# PHY6222_32_0_4__V1_7.net
KiCad netlist of a schematic drawn in Altium Designer
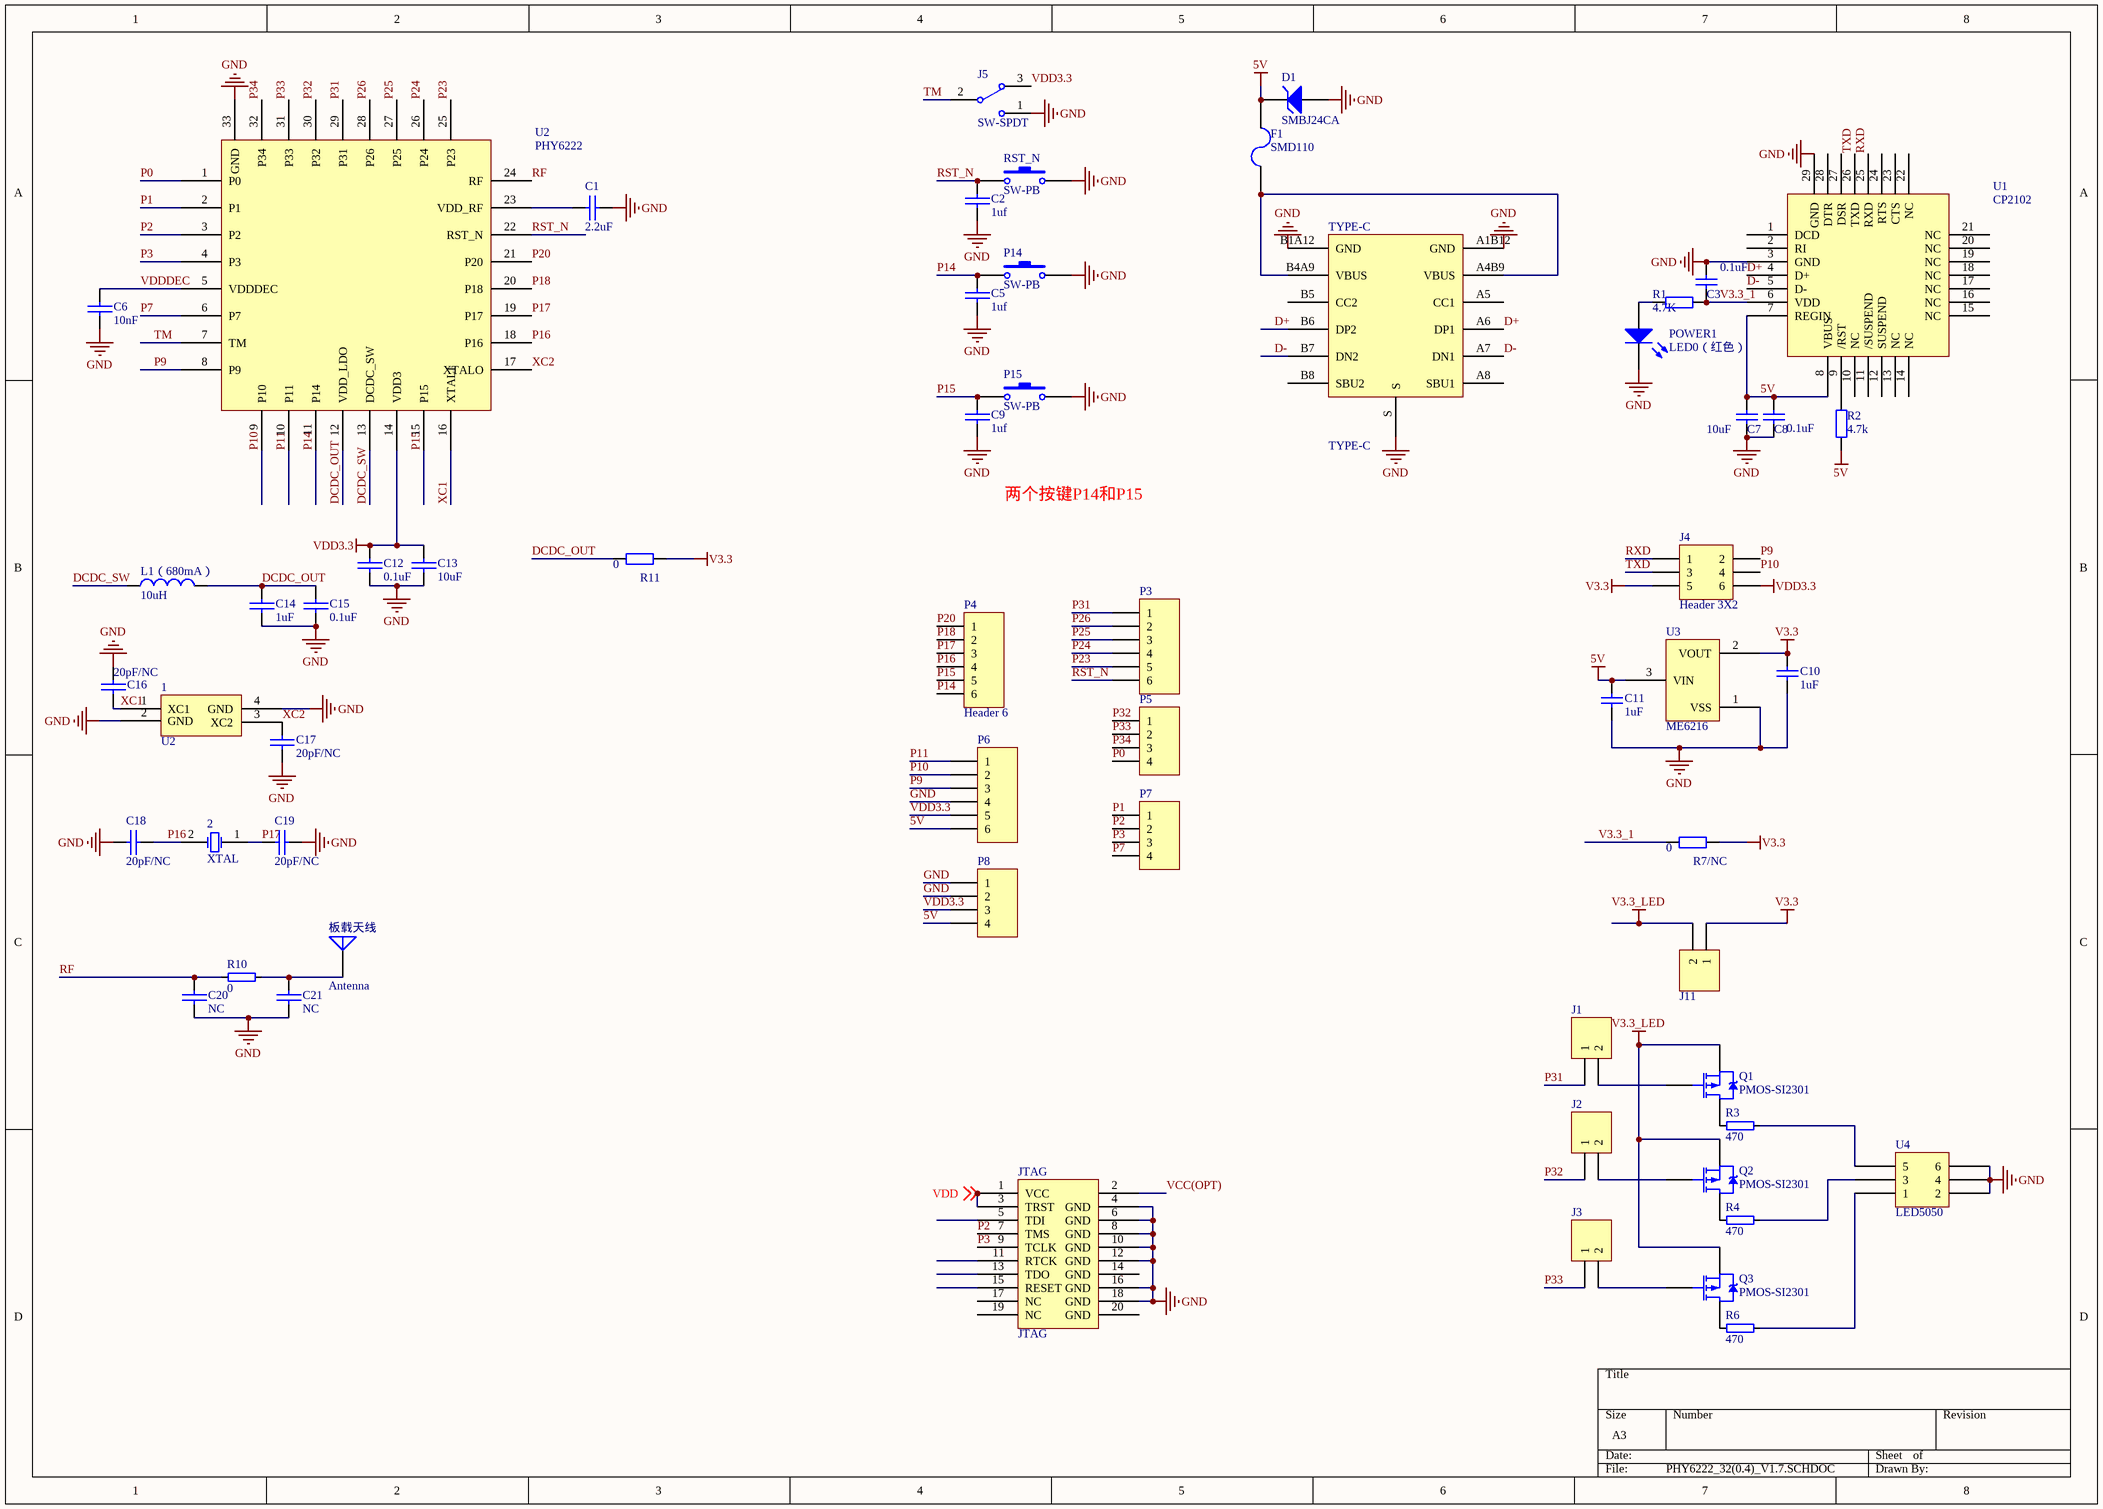
[diagram p0: PHY6222_32(0.4)_V1.7.SCHDOC]

(export (version "E")
  (design (tool "Eeschema 10.0.6"))
  (components
    (comp (ref "1") (value "U2") (footprint "3225") (libsource (lib "RF_APP") (part "3225")))
    (comp (ref "2")
      (value "XTAL")
      (footprint "3215   32.768k")
      (description "Crystal Oscillator")
      (fields (field (name "PUBLISHER") "Altium Limited"))
      (libsource (lib "Miscellaneous Devices") (part "XTAL"))
    )
    (comp (ref "C1") (value "2.2uF") (footprint "C0402") (libsource (lib "RF_0603") (part "电容瓷片")))
    (comp (ref "C2") (value "1uf") (footprint "C0402") (libsource (lib "PCB_Project") (part "电容瓷片")))
    (comp (ref "C3")
      (value "0.1uF")
      (footprint "C0402")
      (description "Capacitor")
      (fields (field (name "PUBLISHER") "Altium Limited"))
      (libsource (lib "Miscellaneous Devices") (part "Cap"))
    )
    (comp (ref "C5") (value "1uf") (footprint "C0402") (libsource (lib "PCB_Project") (part "电容瓷片")))
    (comp (ref "C6") (value "10nF") (footprint "C0402") (libsource (lib "RF_0603") (part "电容瓷片")))
    (comp (ref "C7")
      (value "10uF")
      (footprint "0603R")
      (description "Capacitor")
      (fields (field (name "PUBLISHER") "Altium Limited"))
      (libsource (lib "Miscellaneous Devices") (part "Cap"))
    )
    (comp (ref "C8")
      (value "0.1uF")
      (footprint "C0402")
      (description "Capacitor")
      (fields (field (name "PUBLISHER") "Altium Limited"))
      (libsource (lib "Miscellaneous Devices") (part "Cap"))
    )
    (comp (ref "C9") (value "1uf") (footprint "C0402") (libsource (lib "PCB_Project") (part "电容瓷片")))
    (comp (ref "C10")
      (value "1uF")
      (footprint "C0402")
      (description "Capacitor")
      (fields (field (name "PUBLISHER") "Altium Limited"))
      (libsource (lib "Miscellaneous Devices") (part "Cap"))
    )
    (comp (ref "C11")
      (value "1uF")
      (footprint "C0402")
      (description "Capacitor")
      (fields (field (name "PUBLISHER") "Altium Limited"))
      (libsource (lib "Miscellaneous Devices") (part "Cap"))
    )
    (comp (ref "C12") (value "0.1uF") (footprint "C0402") (libsource (lib "PCB_Project") (part "电容瓷片")))
    (comp (ref "C13") (value "10uF") (footprint "C0603") (libsource (lib "PCB_Project") (part "电容瓷片")))
    (comp (ref "C14") (value "1uF") (footprint "C0402") (libsource (lib "RF_0603") (part "电容瓷片")))
    (comp (ref "C15") (value "0.1uF") (footprint "C0402") (libsource (lib "RF_0603") (part "电容瓷片")))
    (comp (ref "C16") (value "20pF/NC") (footprint "C0402") (libsource (lib "PCB_Project") (part "电容瓷片")))
    (comp (ref "C17") (value "20pF/NC") (footprint "C0402") (libsource (lib "PCB_Project") (part "电容瓷片")))
    (comp (ref "C18") (value "20pF/NC") (footprint "C0402") (libsource (lib "PCB_Project") (part "电容瓷片")))
    (comp (ref "C19") (value "20pF/NC") (footprint "C0402") (libsource (lib "PCB_Project") (part "电容瓷片")))
    (comp (ref "C20") (value "NC") (footprint "C0402") (libsource (lib "RF_0603") (part "电容瓷片")))
    (comp (ref "C21") (value "NC") (footprint "C0402") (libsource (lib "RF_0603") (part "电容瓷片")))
    (comp (ref "D1")
      (value "SMBJ24CA")
      (footprint "1N5819S")
      (description "Zener Diode")
      (fields (field (name "PUBLISHER") "*"))
      (libsource (lib "*") (part "D Zener"))
    )
    (comp (ref "F1")
      (value "SMD110")
      (footprint "1812")
      (description "Fuse")
      (libsource (lib "RC-sheet") (part "FUSE2"))
    )
    (comp (ref "J1")
      (value "Header 2")
      (footprint "HDR1X2")
      (description "Header, 2-Pin")
      (fields (field (name "PUBLISHER") "Altium Limited"))
      (libsource (lib "Miscellaneous Connectors") (part "Header 2"))
    )
    (comp (ref "J2")
      (value "Header 2")
      (footprint "HDR1X2")
      (description "Header, 2-Pin")
      (fields (field (name "PUBLISHER") "Altium Limited"))
      (libsource (lib "Miscellaneous Connectors") (part "Header 2"))
    )
    (comp (ref "J3")
      (value "Header 2")
      (footprint "HDR1X2")
      (description "Header, 2-Pin")
      (fields (field (name "PUBLISHER") "Altium Limited"))
      (libsource (lib "Miscellaneous Connectors") (part "Header 2"))
    )
    (comp (ref "J4")
      (value "Header 3X2")
      (footprint "HDR2X3")
      (description "Header, 3-Pin, Dual row")
      (fields (field (name "PUBLISHER") "Altium Limited"))
      (libsource (lib "Miscellaneous Connectors") (part "Header 3X2"))
    )
    (comp (ref "J5")
      (value "SW-SPDT")
      (footprint "HDR1X3")
      (description "SPDT Subminiature Toggle Switch, Right Angle Mounting, Vertical Actuation")
      (fields (field (name "PUBLISHER") "Altium Limited"))
      (libsource (lib "Miscellaneous Devices") (part "SW-SPDT"))
    )
    (comp (ref "J11")
      (value "Header 2")
      (footprint "HDR1X2")
      (description "Header, 2-Pin")
      (fields (field (name "PUBLISHER") "Altium Limited"))
      (libsource (lib "") (part "Header 2_1"))
    )
    (comp (ref "JTAG") (value "JTAG") (footprint "JTAG1") (libsource (lib "PCB_Project") (part "JTAG")))
    (comp (ref "L1（680mA）")
      (value "10uH")
      (footprint "SMD2520")
      (description "电感")
      (fields (field (name "PUBLISHER") "Altium Limited"))
      (libsource (lib "RF_0603") (part "电感"))
    )
    (comp (ref "P3")
      (value "MHDR1X6")
      (footprint "HDR1X6")
      (description "Header, 6-Pin")
      (fields (field (name "PUBLISHER") "Altium Limited"))
      (libsource (lib "Miscellaneous Connectors") (part "MHDR1X6"))
    )
    (comp (ref "P4")
      (value "Header 6")
      (footprint "HDR1X6")
      (description "Header, 6-Pin")
      (fields (field (name "PUBLISHER") "Altium Limited"))
      (libsource (lib "Phyplus") (part "Header 6"))
    )
    (comp (ref "P5")
      (value "MHDR1X4")
      (footprint "HDR1X4")
      (description "Header, 4-Pin")
      (fields (field (name "PUBLISHER") "Altium Limited"))
      (libsource (lib "Miscellaneous Connectors") (part "MHDR1X4"))
    )
    (comp (ref "P6")
      (value "MHDR1X6")
      (footprint "HDR1X6")
      (description "Header, 6-Pin")
      (fields (field (name "PUBLISHER") "Altium Limited"))
      (libsource (lib "Miscellaneous Connectors") (part "MHDR1X6"))
    )
    (comp (ref "P7")
      (value "MHDR1X4")
      (footprint "HDR1X4")
      (description "Header, 4-Pin")
      (fields (field (name "PUBLISHER") "Altium Limited"))
      (libsource (lib "Miscellaneous Connectors") (part "MHDR1X4"))
    )
    (comp (ref "P8")
      (value "MHDR1X4")
      (footprint "HDR1X4")
      (description "Header, 4-Pin")
      (fields (field (name "PUBLISHER") "Altium Limited"))
      (libsource (lib "Miscellaneous Connectors") (part "MHDR1X4"))
    )
    (comp (ref "P14")
      (value "SW-PB")
      (footprint "SW  3*4*2")
      (description "Switch")
      (fields (field (name "PUBLISHER") "Altium Limited"))
      (libsource (lib "Miscellaneous Devices") (part "SW-PB"))
    )
    (comp (ref "P15")
      (value "SW-PB")
      (footprint "SW  3*4*2")
      (description "Switch")
      (fields (field (name "PUBLISHER") "Altium Limited"))
      (libsource (lib "Miscellaneous Devices") (part "SW-PB"))
    )
    (comp (ref "POWER1")
      (value "LED0（红色）")
      (footprint "LED0603")
      (description "Typical INFRARED GaAs LED")
      (fields (field (name "PUBLISHER") "Altium Limited"))
      (libsource (lib "Miscellaneous Devices") (part "LED0"))
    )
    (comp (ref "Q1")
      (value "PMOS-SI2301")
      (footprint "SOT-23")
      (description "P-Channel Power MOSFET")
      (fields (field (name "PUBLISHER") "Altium Limited"))
      (libsource (lib "Miscellaneous Devices") (part "PMOS-2"))
    )
    (comp (ref "Q2")
      (value "PMOS-SI2301")
      (footprint "SOT-23")
      (description "P-Channel Power MOSFET")
      (fields (field (name "PUBLISHER") "Altium Limited"))
      (libsource (lib "Miscellaneous Devices") (part "PMOS-2"))
    )
    (comp (ref "Q3")
      (value "PMOS-SI2301")
      (footprint "SOT-23")
      (description "P-Channel Power MOSFET")
      (fields (field (name "PUBLISHER") "Altium Limited"))
      (libsource (lib "Miscellaneous Devices") (part "PMOS-2"))
    )
    (comp (ref "R1")
      (value "4.7K")
      (footprint "R0402")
      (description "Resistor")
      (fields (field (name "PUBLISHER") "Altium Limited"))
      (libsource (lib "") (part "Res2_1"))
    )
    (comp (ref "R2")
      (value "4.7k")
      (footprint "R0402")
      (description "Resistor")
      (fields (field (name "PUBLISHER") "Altium Limited"))
      (libsource (lib "Miscellaneous Devices") (part "Res2"))
    )
    (comp (ref "R3") (value "470") (footprint "R0402") (libsource (lib "RF_0603") (part "电阻贴片")))
    (comp (ref "R4") (value "470") (footprint "R0402") (libsource (lib "RF_0603") (part "电阻贴片")))
    (comp (ref "R6") (value "470") (footprint "R0402") (libsource (lib "RF_0603") (part "电阻贴片")))
    (comp (ref "R7/NC")
      (value "0")
      (footprint "R0603")
      (description "Resistor")
      (fields (field (name "Comment") "4.7K") (field (name "PUBLISHER") "Altium Limited"))
      (libsource (lib "") (part "Res2_1"))
    )
    (comp (ref "R10") (value "0") (footprint "R0402") (libsource (lib "RF_0603") (part "电阻贴片")))
    (comp (ref "R11")
      (value "0")
      (footprint "R0603")
      (description "Resistor")
      (fields (field (name "Comment") "4.7K") (field (name "PUBLISHER") "Altium Limited"))
      (libsource (lib "") (part "Res2_1"))
    )
    (comp (ref "RST_N")
      (value "SW-PB")
      (footprint "SW  3*4*2")
      (description "Switch")
      (fields (field (name "PUBLISHER") "Altium Limited"))
      (libsource (lib "Miscellaneous Devices") (part "SW-PB"))
    )
    (comp (ref "TYPE-C") (value "TYPE-C") (footprint "TYPE-C") (libsource (lib "Phyplus") (part "TYPE-C")))
    (comp (ref "U1") (value "CP2102") (footprint "CP2102") (libsource (lib "Phyplus") (part "cp2102")))
    (comp (ref "U2")
      (value "PHY6222")
      (footprint "QFN32_0.4")
      (libsource (lib "Phyplus") (part "QFN32-1202"))
    )
    (comp (ref "U3") (value "ME6216") (footprint "SOT-23") (libsource (lib "Phyplus") (part "ME6216")))
    (comp (ref "U4") (value "LED5050") (footprint "LED5050") (libsource (lib "PCB_Project") (part "LED5050")))
    (comp (ref "板载天线")
      (value "Antenna")
      (footprint "PIN1")
      (description "Generic Antenna")
      (fields (field (name "PUBLISHER") "Altium Limited"))
      (libsource (lib "Miscellaneous Devices") (part "Antenna"))
    )
  )
  (nets
    (net (code "1") (name "/D+") (class "Default")
      (node (ref "TYPE-C") (pin "A6") (pinfunction "DP1_A6") (pintype "passive"))
      (node (ref "TYPE-C") (pin "B6") (pinfunction "DP2_B6") (pintype "passive"))
      (node (ref "U1") (pin "4") (pinfunction "D+_4") (pintype "passive"))
    )
    (net (code "2") (name "/D-") (class "Default")
      (node (ref "TYPE-C") (pin "A7") (pinfunction "DN1_A7") (pintype "passive"))
      (node (ref "TYPE-C") (pin "B7") (pinfunction "DN2_B7") (pintype "passive"))
      (node (ref "U1") (pin "5") (pinfunction "D-_5") (pintype "passive"))
    )
    (net (code "3") (name "/DCDC_OUT") (class "Default")
      (node (ref "C14") (pin "1") (pinfunction "1_1") (pintype "passive"))
      (node (ref "C15") (pin "1") (pinfunction "1_1") (pintype "passive"))
      (node (ref "L1（680mA）") (pin "2") (pinfunction "2_2") (pintype "passive"))
      (node (ref "R11") (pin "1") (pinfunction "1_1") (pintype "passive"))
      (node (ref "U2") (pin "12") (pinfunction "VDD_LDO_12") (pintype "passive"))
    )
    (net (code "4") (name "/DCDC_SW") (class "Default")
      (node (ref "L1（680mA）") (pin "1") (pinfunction "1_1") (pintype "passive"))
      (node (ref "U2") (pin "13") (pinfunction "DCDC_SW_13") (pintype "passive"))
    )
    (net (code "5") (name "/P0") (class "Default")
      (node (ref "P5") (pin "4") (pinfunction "4_4") (pintype "passive"))
      (node (ref "U2") (pin "1") (pinfunction "P0_1") (pintype "passive"))
    )
    (net (code "6") (name "/P1") (class "Default")
      (node (ref "P7") (pin "1") (pinfunction "1_1") (pintype "passive"))
      (node (ref "U2") (pin "2") (pinfunction "P1_2") (pintype "passive"))
    )
    (net (code "7") (name "/P2") (class "Default")
      (node (ref "JTAG") (pin "7") (pinfunction "TMS_7") (pintype "passive"))
      (node (ref "P7") (pin "2") (pinfunction "2_2") (pintype "passive"))
      (node (ref "U2") (pin "3") (pinfunction "P2_3") (pintype "passive"))
    )
    (net (code "8") (name "/P3") (class "Default")
      (node (ref "JTAG") (pin "9") (pinfunction "TCLK_9") (pintype "passive"))
      (node (ref "P7") (pin "3") (pinfunction "3_3") (pintype "passive"))
      (node (ref "U2") (pin "4") (pinfunction "P3_4") (pintype "passive"))
    )
    (net (code "9") (name "/P7") (class "Default")
      (node (ref "P7") (pin "4") (pinfunction "4_4") (pintype "passive"))
      (node (ref "U2") (pin "6") (pinfunction "P7_6") (pintype "passive"))
    )
    (net (code "10") (name "/P9") (class "Default")
      (node (ref "J4") (pin "2") (pinfunction "2_2") (pintype "passive"))
      (node (ref "P6") (pin "3") (pinfunction "3_3") (pintype "passive"))
      (node (ref "U2") (pin "8") (pinfunction "P9_8") (pintype "passive"))
    )
    (net (code "11") (name "/P10") (class "Default")
      (node (ref "J4") (pin "4") (pinfunction "4_4") (pintype "passive"))
      (node (ref "P6") (pin "2") (pinfunction "2_2") (pintype "passive"))
      (node (ref "U2") (pin "9") (pinfunction "P10_9") (pintype "passive"))
    )
    (net (code "12") (name "/P11") (class "Default")
      (node (ref "P6") (pin "1") (pinfunction "1_1") (pintype "passive"))
      (node (ref "U2") (pin "10") (pinfunction "P11_10") (pintype "passive"))
    )
    (net (code "13") (name "/P14") (class "Default")
      (node (ref "C5") (pin "1") (pinfunction "1_1") (pintype "passive"))
      (node (ref "P14") (pin "1") (pinfunction "1_1") (pintype "passive"))
      (node (ref "P4") (pin "6") (pinfunction "6_6") (pintype "passive"))
      (node (ref "U2") (pin "11") (pinfunction "P14_11") (pintype "passive"))
    )
    (net (code "14") (name "/P15") (class "Default")
      (node (ref "C9") (pin "1") (pinfunction "1_1") (pintype "passive"))
      (node (ref "P15") (pin "1") (pinfunction "1_1") (pintype "passive"))
      (node (ref "P4") (pin "5") (pinfunction "5_5") (pintype "passive"))
      (node (ref "U2") (pin "15") (pinfunction "P15_15") (pintype "passive"))
    )
    (net (code "15") (name "/P16") (class "Default")
      (node (ref "2") (pin "2") (pinfunction "OSC2_2") (pintype "passive"))
      (node (ref "C18") (pin "2") (pinfunction "2_2") (pintype "passive"))
      (node (ref "P4") (pin "4") (pinfunction "4_4") (pintype "passive"))
      (node (ref "U2") (pin "18") (pinfunction "P16_18") (pintype "passive"))
    )
    (net (code "16") (name "/P17") (class "Default")
      (node (ref "2") (pin "1") (pinfunction "OSC1_1") (pintype "passive"))
      (node (ref "C19") (pin "2") (pinfunction "2_2") (pintype "passive"))
      (node (ref "P4") (pin "3") (pinfunction "3_3") (pintype "passive"))
      (node (ref "U2") (pin "19") (pinfunction "P17_19") (pintype "passive"))
    )
    (net (code "17") (name "/P18") (class "Default")
      (node (ref "P4") (pin "2") (pinfunction "2_2") (pintype "passive"))
      (node (ref "U2") (pin "20") (pinfunction "P18_20") (pintype "passive"))
    )
    (net (code "18") (name "/P20") (class "Default")
      (node (ref "P4") (pin "1") (pinfunction "1_1") (pintype "passive"))
      (node (ref "U2") (pin "21") (pinfunction "P20_21") (pintype "passive"))
    )
    (net (code "19") (name "/P23") (class "Default")
      (node (ref "P3") (pin "5") (pinfunction "5_5") (pintype "passive"))
      (node (ref "U2") (pin "25") (pinfunction "P23_25") (pintype "passive"))
    )
    (net (code "20") (name "/P24") (class "Default")
      (node (ref "P3") (pin "4") (pinfunction "4_4") (pintype "passive"))
      (node (ref "U2") (pin "26") (pinfunction "P24_26") (pintype "passive"))
    )
    (net (code "21") (name "/P25") (class "Default")
      (node (ref "P3") (pin "3") (pinfunction "3_3") (pintype "passive"))
      (node (ref "U2") (pin "27") (pinfunction "P25_27") (pintype "passive"))
    )
    (net (code "22") (name "/P26") (class "Default")
      (node (ref "P3") (pin "2") (pinfunction "2_2") (pintype "passive"))
      (node (ref "U2") (pin "28") (pinfunction "P26_28") (pintype "passive"))
    )
    (net (code "23") (name "/P31") (class "Default")
      (node (ref "J1") (pin "1") (pinfunction "1_1") (pintype "passive"))
      (node (ref "P3") (pin "1") (pinfunction "1_1") (pintype "passive"))
      (node (ref "U2") (pin "29") (pinfunction "P31_29") (pintype "passive"))
    )
    (net (code "24") (name "/P32") (class "Default")
      (node (ref "J2") (pin "1") (pinfunction "1_1") (pintype "passive"))
      (node (ref "P5") (pin "1") (pinfunction "1_1") (pintype "passive"))
      (node (ref "U2") (pin "30") (pinfunction "P32_30") (pintype "passive"))
    )
    (net (code "25") (name "/P33") (class "Default")
      (node (ref "J3") (pin "1") (pinfunction "1_1") (pintype "passive"))
      (node (ref "P5") (pin "2") (pinfunction "2_2") (pintype "passive"))
      (node (ref "U2") (pin "31") (pinfunction "P33_31") (pintype "passive"))
    )
    (net (code "26") (name "/P34") (class "Default")
      (node (ref "P5") (pin "3") (pinfunction "3_3") (pintype "passive"))
      (node (ref "U2") (pin "32") (pinfunction "P34_32") (pintype "passive"))
    )
    (net (code "27") (name "/RF") (class "Default")
      (node (ref "C20") (pin "1") (pinfunction "1_1") (pintype "passive"))
      (node (ref "R10") (pin "1") (pinfunction "1_1") (pintype "passive"))
      (node (ref "U2") (pin "24") (pinfunction "RF_24") (pintype "passive"))
    )
    (net (code "28") (name "/RST_N") (class "Default")
      (node (ref "C2") (pin "1") (pinfunction "1_1") (pintype "passive"))
      (node (ref "P3") (pin "6") (pinfunction "6_6") (pintype "passive"))
      (node (ref "RST_N") (pin "1") (pinfunction "1_1") (pintype "passive"))
      (node (ref "U2") (pin "22") (pinfunction "RST_N_22") (pintype "passive"))
    )
    (net (code "29") (name "/RXD") (class "Default")
      (node (ref "J4") (pin "1") (pinfunction "1_1") (pintype "passive"))
      (node (ref "U1") (pin "25") (pinfunction "RXD_25") (pintype "passive"))
    )
    (net (code "30") (name "/TM") (class "Default")
      (node (ref "J5") (pin "2") (pinfunction "2_2") (pintype "passive"))
      (node (ref "U2") (pin "7") (pinfunction "TM_7") (pintype "passive"))
    )
    (net (code "31") (name "/TXD") (class "Default")
      (node (ref "J4") (pin "3") (pinfunction "3_3") (pintype "passive"))
      (node (ref "U1") (pin "26") (pinfunction "TXD_26") (pintype "passive"))
    )
    (net (code "32") (name "/V3.3_1") (class "Default")
      (node (ref "C3") (pin "1") (pinfunction "1_1") (pintype "passive"))
      (node (ref "R1") (pin "2") (pinfunction "2_2") (pintype "passive"))
      (node (ref "R7/NC") (pin "1") (pinfunction "1_1") (pintype "passive"))
      (node (ref "U1") (pin "6") (pinfunction "VDD_6") (pintype "passive"))
    )
    (net (code "33") (name "/VCC(OPT)") (class "Default") (node (ref "JTAG") (pin "2") (pintype "passive")))
    (net (code "34") (name "/VDDDEC") (class "Default")
      (node (ref "C6") (pin "1") (pinfunction "1_1") (pintype "passive"))
      (node (ref "U2") (pin "5") (pinfunction "VDDDEC_5") (pintype "passive"))
    )
    (net (code "35") (name "/XC1") (class "Default")
      (node (ref "1") (pin "1") (pinfunction "XC1_1") (pintype "passive"))
      (node (ref "C16") (pin "2") (pinfunction "2_2") (pintype "passive"))
      (node (ref "U2") (pin "16") (pinfunction "XTALI_16") (pintype "passive"))
    )
    (net (code "36") (name "/XC2") (class "Default")
      (node (ref "1") (pin "3") (pinfunction "XC2_3") (pintype "passive"))
      (node (ref "C17") (pin "2") (pinfunction "2_2") (pintype "passive"))
      (node (ref "U2") (pin "17") (pinfunction "XTALO_17") (pintype "passive"))
    )
    (net (code "37") (name "5V") (class "Default")
      (node (ref "C11") (pin "1") (pinfunction "1_1") (pintype "passive"))
      (node (ref "C7") (pin "2") (pinfunction "2_2") (pintype "passive"))
      (node (ref "C8") (pin "2") (pinfunction "2_2") (pintype "passive"))
      (node (ref "D1") (pin "2") (pinfunction "K_2") (pintype "passive"))
      (node (ref "F1") (pin "2") (pinfunction "2_2") (pintype "passive"))
      (node (ref "P6") (pin "6") (pinfunction "6_6") (pintype "passive"))
      (node (ref "P8") (pin "4") (pinfunction "4_4") (pintype "passive"))
      (node (ref "R2") (pin "1") (pinfunction "1_1") (pintype "passive"))
      (node (ref "U1") (pin "7") (pinfunction "REGIN_7") (pintype "passive"))
      (node (ref "U1") (pin "8") (pinfunction "VBUS_8") (pintype "passive"))
      (node (ref "U3") (pin "3") (pinfunction "VIN_3") (pintype "passive"))
    )
    (net (code "38") (name "GND") (class "Default")
      (node (ref "1") (pin "2") (pinfunction "GND_2") (pintype "passive"))
      (node (ref "1") (pin "4") (pinfunction "GND_4") (pintype "passive"))
      (node (ref "C1") (pin "2") (pinfunction "2_2") (pintype "passive"))
      (node (ref "C10") (pin "2") (pinfunction "2_2") (pintype "passive"))
      (node (ref "C11") (pin "2") (pinfunction "2_2") (pintype "passive"))
      (node (ref "C12") (pin "2") (pinfunction "2_2") (pintype "passive"))
      (node (ref "C13") (pin "2") (pinfunction "2_2") (pintype "passive"))
      (node (ref "C14") (pin "2") (pinfunction "2_2") (pintype "passive"))
      (node (ref "C15") (pin "2") (pinfunction "2_2") (pintype "passive"))
      (node (ref "C16") (pin "1") (pinfunction "1_1") (pintype "passive"))
      (node (ref "C17") (pin "1") (pinfunction "1_1") (pintype "passive"))
      (node (ref "C18") (pin "1") (pinfunction "1_1") (pintype "passive"))
      (node (ref "C19") (pin "1") (pinfunction "1_1") (pintype "passive"))
      (node (ref "C2") (pin "2") (pinfunction "2_2") (pintype "passive"))
      (node (ref "C20") (pin "2") (pinfunction "2_2") (pintype "passive"))
      (node (ref "C21") (pin "2") (pinfunction "2_2") (pintype "passive"))
      (node (ref "C3") (pin "2") (pinfunction "2_2") (pintype "passive"))
      (node (ref "C5") (pin "2") (pinfunction "2_2") (pintype "passive"))
      (node (ref "C6") (pin "2") (pinfunction "2_2") (pintype "passive"))
      (node (ref "C7") (pin "1") (pinfunction "1_1") (pintype "passive"))
      (node (ref "C8") (pin "1") (pinfunction "1_1") (pintype "passive"))
      (node (ref "C9") (pin "2") (pinfunction "2_2") (pintype "passive"))
      (node (ref "D1") (pin "1") (pinfunction "A_1") (pintype "passive"))
      (node (ref "J5") (pin "1") (pinfunction "1_1") (pintype "passive"))
      (node (ref "JTAG") (pin "10") (pinfunction "GND_10") (pintype "passive"))
      (node (ref "JTAG") (pin "12") (pinfunction "GND_12") (pintype "passive"))
      (node (ref "JTAG") (pin "16") (pinfunction "GND_16") (pintype "passive"))
      (node (ref "JTAG") (pin "18") (pinfunction "GND_18") (pintype "passive"))
      (node (ref "JTAG") (pin "4") (pinfunction "GND_4") (pintype "passive"))
      (node (ref "JTAG") (pin "6") (pinfunction "GND_6") (pintype "passive"))
      (node (ref "JTAG") (pin "8") (pinfunction "GND_8") (pintype "passive"))
      (node (ref "P14") (pin "2") (pinfunction "2_2") (pintype "passive"))
      (node (ref "P15") (pin "2") (pinfunction "2_2") (pintype "passive"))
      (node (ref "P6") (pin "4") (pinfunction "4_4") (pintype "passive"))
      (node (ref "P8") (pin "1") (pinfunction "1_1") (pintype "passive"))
      (node (ref "P8") (pin "2") (pinfunction "2_2") (pintype "passive"))
      (node (ref "POWER1") (pin "2") (pinfunction "K_2") (pintype "passive"))
      (node (ref "RST_N") (pin "2") (pinfunction "2_2") (pintype "passive"))
      (node (ref "TYPE-C") (pin "A1B12") (pinfunction "GND_A1B12") (pintype "passive"))
      (node (ref "TYPE-C") (pin "B1A12") (pinfunction "GND_B1A12") (pintype "passive"))
      (node (ref "TYPE-C") (pin "S") (pinfunction "S_S") (pintype "passive"))
      (node (ref "U1") (pin "29") (pinfunction "GND_29") (pintype "passive"))
      (node (ref "U1") (pin "3") (pinfunction "GND_3") (pintype "passive"))
      (node (ref "U2") (pin "33") (pinfunction "GND_33") (pintype "passive"))
      (node (ref "U3") (pin "1") (pinfunction "VSS_1") (pintype "passive"))
      (node (ref "U4") (pin "2") (pinfunction "2_2") (pintype "passive"))
      (node (ref "U4") (pin "4") (pinfunction "4_4") (pintype "passive"))
      (node (ref "U4") (pin "6") (pinfunction "6_6") (pintype "passive"))
    )
    (net (code "39") (name "Net-(F1-Pad1)") (class "Default")
      (node (ref "F1") (pin "1") (pinfunction "1_1") (pintype "passive"))
      (node (ref "TYPE-C") (pin "A4B9") (pinfunction "VBUS_A4B9") (pintype "passive"))
      (node (ref "TYPE-C") (pin "B4A9") (pinfunction "VBUS_B4A9") (pintype "passive"))
    )
    (net (code "40") (name "Net-(POWER1-A)") (class "Default")
      (node (ref "POWER1") (pin "1") (pinfunction "A_1") (pintype "passive"))
      (node (ref "R1") (pin "1") (pinfunction "1_1") (pintype "passive"))
    )
    (net (code "41") (name "Net-(Q1-D)") (class "Default")
      (node (ref "Q1") (pin "2") (pinfunction "D_2") (pintype "passive"))
      (node (ref "R3") (pin "1") (pinfunction "1_1") (pintype "passive"))
    )
    (net (code "42") (name "Net-(Q1-G)") (class "Default")
      (node (ref "J1") (pin "2") (pinfunction "2_2") (pintype "passive"))
      (node (ref "Q1") (pin "1") (pinfunction "G_1") (pintype "passive"))
    )
    (net (code "43") (name "Net-(Q2-D)") (class "Default")
      (node (ref "Q2") (pin "2") (pinfunction "D_2") (pintype "passive"))
      (node (ref "R4") (pin "1") (pinfunction "1_1") (pintype "passive"))
    )
    (net (code "44") (name "Net-(Q2-G)") (class "Default")
      (node (ref "J2") (pin "2") (pinfunction "2_2") (pintype "passive"))
      (node (ref "Q2") (pin "1") (pinfunction "G_1") (pintype "passive"))
    )
    (net (code "45") (name "Net-(Q3-D)") (class "Default")
      (node (ref "Q3") (pin "2") (pinfunction "D_2") (pintype "passive"))
      (node (ref "R6") (pin "1") (pinfunction "1_1") (pintype "passive"))
    )
    (net (code "46") (name "Net-(Q3-G)") (class "Default")
      (node (ref "J3") (pin "2") (pinfunction "2_2") (pintype "passive"))
      (node (ref "Q3") (pin "1") (pinfunction "G_1") (pintype "passive"))
    )
    (net (code "47") (name "Net-(R3-Pad2)") (class "Default")
      (node (ref "R3") (pin "2") (pinfunction "2_2") (pintype "passive"))
      (node (ref "U4") (pin "5") (pinfunction "5_5") (pintype "passive"))
    )
    (net (code "48") (name "Net-(R4-Pad2)") (class "Default")
      (node (ref "R4") (pin "2") (pinfunction "2_2") (pintype "passive"))
      (node (ref "U4") (pin "3") (pinfunction "3_3") (pintype "passive"))
    )
    (net (code "49") (name "Net-(R6-Pad2)") (class "Default")
      (node (ref "R6") (pin "2") (pinfunction "2_2") (pintype "passive"))
      (node (ref "U4") (pin "1") (pinfunction "1_1") (pintype "passive"))
    )
    (net (code "50") (name "Net-(U1-{slash}RST)") (class "Default")
      (node (ref "R2") (pin "2") (pinfunction "2_2") (pintype "passive"))
      (node (ref "U1") (pin "9") (pinfunction "/RST_9") (pintype "passive"))
    )
    (net (code "51") (name "Net-(U2-VDD_RF)") (class "Default")
      (node (ref "C1") (pin "1") (pinfunction "1_1") (pintype "passive"))
      (node (ref "U2") (pin "23") (pinfunction "VDD_RF_23") (pintype "passive"))
    )
    (net (code "52") (name "Net-(板载天线-A)") (class "Default")
      (node (ref "C21") (pin "1") (pinfunction "1_1") (pintype "passive"))
      (node (ref "R10") (pin "2") (pinfunction "2_2") (pintype "passive"))
      (node (ref "板载天线") (pin "1") (pinfunction "A_1") (pintype "passive"))
    )
    (net (code "53") (name "V3.3") (class "Default")
      (node (ref "C10") (pin "1") (pinfunction "1_1") (pintype "passive"))
      (node (ref "J11") (pin "1") (pinfunction "1_1") (pintype "passive"))
      (node (ref "J4") (pin "5") (pinfunction "5_5") (pintype "passive"))
      (node (ref "R11") (pin "2") (pinfunction "2_2") (pintype "passive"))
      (node (ref "R7/NC") (pin "2") (pinfunction "2_2") (pintype "passive"))
      (node (ref "U3") (pin "2") (pinfunction "VOUT_2") (pintype "passive"))
    )
    (net (code "54") (name "V3.3_LED") (class "Default")
      (node (ref "J11") (pin "2") (pinfunction "2_2") (pintype "passive"))
      (node (ref "Q1") (pin "3") (pinfunction "S_3") (pintype "passive"))
      (node (ref "Q2") (pin "3") (pinfunction "S_3") (pintype "passive"))
      (node (ref "Q3") (pin "3") (pinfunction "S_3") (pintype "passive"))
    )
    (net (code "55") (name "VDD") (class "Default")
      (node (ref "JTAG") (pin "1") (pinfunction "VCC_1") (pintype "passive"))
      (node (ref "JTAG") (pin "3") (pinfunction "TRST_3") (pintype "passive"))
    )
    (net (code "56") (name "VDD3.3") (class "Default")
      (node (ref "C12") (pin "1") (pinfunction "1_1") (pintype "passive"))
      (node (ref "C13") (pin "1") (pinfunction "1_1") (pintype "passive"))
      (node (ref "J4") (pin "6") (pinfunction "6_6") (pintype "passive"))
      (node (ref "J5") (pin "3") (pinfunction "3_3") (pintype "passive"))
      (node (ref "P6") (pin "5") (pinfunction "5_5") (pintype "passive"))
      (node (ref "P8") (pin "3") (pinfunction "3_3") (pintype "passive"))
      (node (ref "U2") (pin "14") (pinfunction "VDD3_14") (pintype "passive"))
    )
    (net (code "57") (name "unconnected-(JTAG-GND-Pad14)") (class "Default")
      (node (ref "JTAG") (pin "14") (pinfunction "GND_14") (pintype "passive"))
    )
    (net (code "58") (name "unconnected-(JTAG-GND-Pad20)") (class "Default")
      (node (ref "JTAG") (pin "20") (pinfunction "GND_20") (pintype "passive"))
    )
    (net (code "59") (name "unconnected-(JTAG-NC-Pad17)") (class "Default")
      (node (ref "JTAG") (pin "17") (pinfunction "NC_17") (pintype "passive"))
    )
    (net (code "60") (name "unconnected-(JTAG-NC-Pad19)") (class "Default")
      (node (ref "JTAG") (pin "19") (pinfunction "NC_19") (pintype "passive"))
    )
    (net (code "61") (name "unconnected-(JTAG-RESET-Pad15)") (class "Default")
      (node (ref "JTAG") (pin "15") (pinfunction "RESET_15") (pintype "passive"))
    )
    (net (code "62") (name "unconnected-(JTAG-RTCK-Pad11)") (class "Default")
      (node (ref "JTAG") (pin "11") (pinfunction "RTCK_11") (pintype "passive"))
    )
    (net (code "63") (name "unconnected-(JTAG-TDI-Pad5)") (class "Default")
      (node (ref "JTAG") (pin "5") (pinfunction "TDI_5") (pintype "passive"))
    )
    (net (code "64") (name "unconnected-(JTAG-TDO-Pad13)") (class "Default")
      (node (ref "JTAG") (pin "13") (pinfunction "TDO_13") (pintype "passive"))
    )
    (net (code "65") (name "unconnected-(TYPE-C-CC1-PadA5)") (class "Default")
      (node (ref "TYPE-C") (pin "A5") (pinfunction "CC1_A5") (pintype "passive"))
    )
    (net (code "66") (name "unconnected-(TYPE-C-CC2-PadB5)") (class "Default")
      (node (ref "TYPE-C") (pin "B5") (pinfunction "CC2_B5") (pintype "passive"))
    )
    (net (code "67") (name "unconnected-(TYPE-C-SBU1-PadA8)") (class "Default")
      (node (ref "TYPE-C") (pin "A8") (pinfunction "SBU1_A8") (pintype "passive"))
    )
    (net (code "68") (name "unconnected-(TYPE-C-SBU2-PadB8)") (class "Default")
      (node (ref "TYPE-C") (pin "B8") (pinfunction "SBU2_B8") (pintype "passive"))
    )
    (net (code "69") (name "unconnected-(U1-CTS-Pad23)") (class "Default")
      (node (ref "U1") (pin "23") (pinfunction "CTS_23") (pintype "passive"))
    )
    (net (code "70") (name "unconnected-(U1-DCD-Pad1)") (class "Default")
      (node (ref "U1") (pin "1") (pinfunction "DCD_1") (pintype "passive"))
    )
    (net (code "71") (name "unconnected-(U1-DSR-Pad27)") (class "Default")
      (node (ref "U1") (pin "27") (pinfunction "DSR_27") (pintype "passive"))
    )
    (net (code "72") (name "unconnected-(U1-DTR-Pad28)") (class "Default")
      (node (ref "U1") (pin "28") (pinfunction "DTR_28") (pintype "passive"))
    )
    (net (code "73") (name "unconnected-(U1-NC-Pad10)") (class "Default")
      (node (ref "U1") (pin "10") (pinfunction "NC_10") (pintype "passive"))
    )
    (net (code "74") (name "unconnected-(U1-NC-Pad13)") (class "Default")
      (node (ref "U1") (pin "13") (pinfunction "NC_13") (pintype "passive"))
    )
    (net (code "75") (name "unconnected-(U1-NC-Pad14)") (class "Default")
      (node (ref "U1") (pin "14") (pinfunction "NC_14") (pintype "passive"))
    )
    (net (code "76") (name "unconnected-(U1-NC-Pad15)") (class "Default")
      (node (ref "U1") (pin "15") (pinfunction "NC_15") (pintype "passive"))
    )
    (net (code "77") (name "unconnected-(U1-NC-Pad16)") (class "Default")
      (node (ref "U1") (pin "16") (pinfunction "NC_16") (pintype "passive"))
    )
    (net (code "78") (name "unconnected-(U1-NC-Pad17)") (class "Default")
      (node (ref "U1") (pin "17") (pinfunction "NC_17") (pintype "passive"))
    )
    (net (code "79") (name "unconnected-(U1-NC-Pad18)") (class "Default")
      (node (ref "U1") (pin "18") (pinfunction "NC_18") (pintype "passive"))
    )
    (net (code "80") (name "unconnected-(U1-NC-Pad19)") (class "Default")
      (node (ref "U1") (pin "19") (pinfunction "NC_19") (pintype "passive"))
    )
    (net (code "81") (name "unconnected-(U1-NC-Pad20)") (class "Default")
      (node (ref "U1") (pin "20") (pinfunction "NC_20") (pintype "passive"))
    )
    (net (code "82") (name "unconnected-(U1-NC-Pad21)") (class "Default")
      (node (ref "U1") (pin "21") (pinfunction "NC_21") (pintype "passive"))
    )
    (net (code "83") (name "unconnected-(U1-NC-Pad22)") (class "Default")
      (node (ref "U1") (pin "22") (pinfunction "NC_22") (pintype "passive"))
    )
    (net (code "84") (name "unconnected-(U1-RI-Pad2)") (class "Default")
      (node (ref "U1") (pin "2") (pinfunction "RI_2") (pintype "passive"))
    )
    (net (code "85") (name "unconnected-(U1-RTS-Pad24)") (class "Default")
      (node (ref "U1") (pin "24") (pinfunction "RTS_24") (pintype "passive"))
    )
    (net (code "86") (name "unconnected-(U1-SUSPEND-Pad12)") (class "Default")
      (node (ref "U1") (pin "12") (pinfunction "SUSPEND_12") (pintype "passive"))
    )
    (net (code "87") (name "unconnected-(U1-{slash}SUSPEND-Pad11)") (class "Default")
      (node (ref "U1") (pin "11") (pinfunction "/SUSPEND_11") (pintype "passive"))
    )
  )
)
